# NodeNadelAdapter.net
KiCad netlist of a schematic drawn in EAGLE
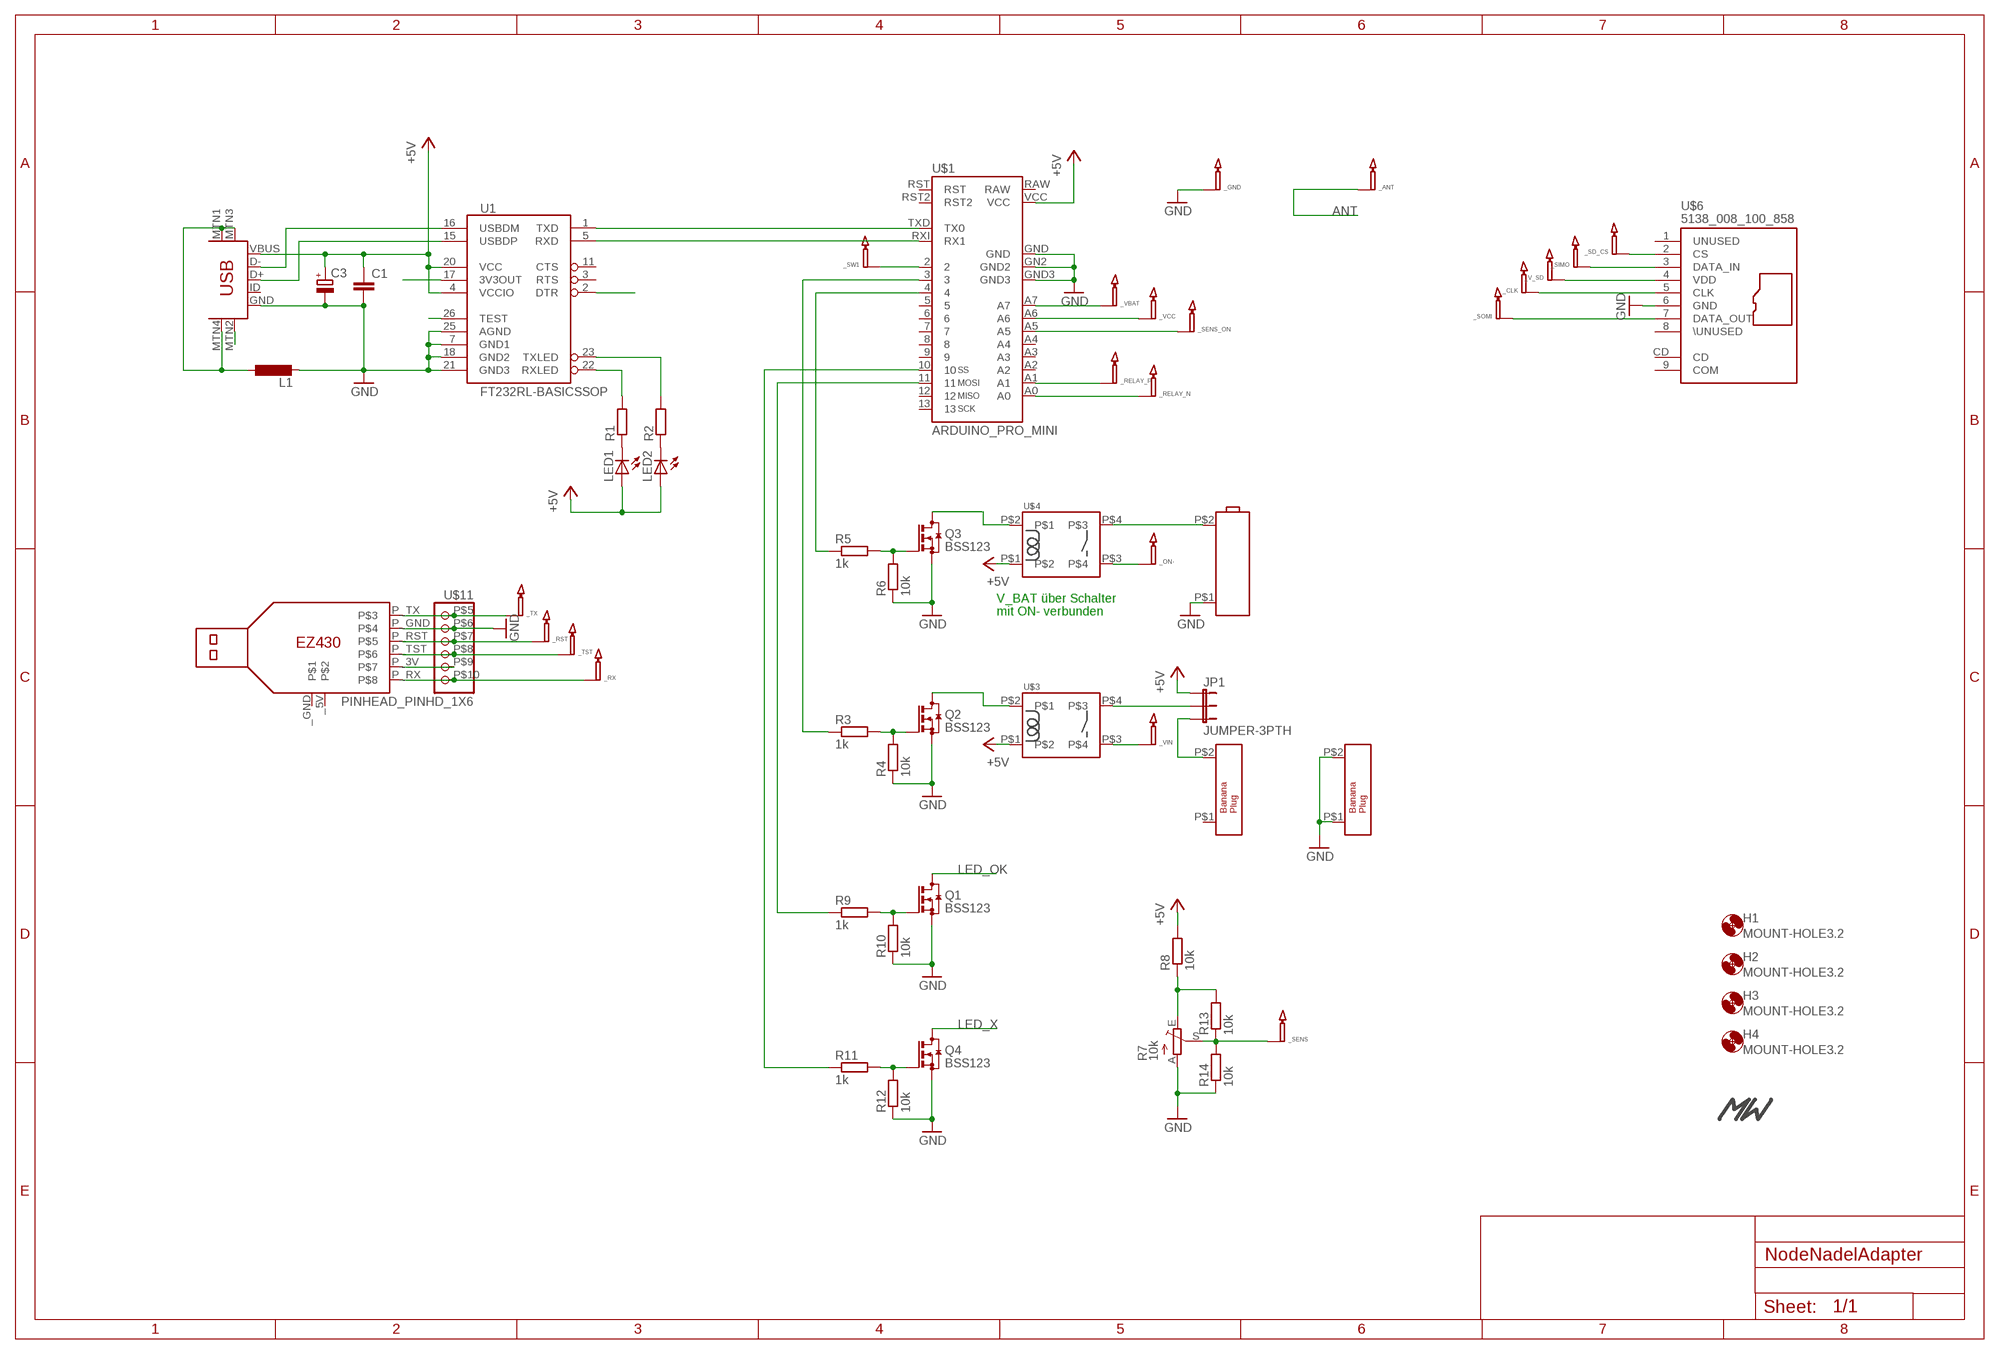
[diagram p0: schematic, sheet 1]

(export (version "E")
  (design (tool "Eeschema 10.0.6"))
  (components
    (comp (ref "C1")
      (value "C-EUC0603")
      (footprint "eagle-import:C0603")
      (libsource (lib "eagle-import") (part "C-EUC0603"))
    )
    (comp (ref "C3")
      (value "CPOL-EUSMCA")
      (footprint "eagle-import:SMC_A")
      (libsource (lib "eagle-import") (part "CPOL-EUSMCA"))
    )
    (comp (ref "H1")
      (value "MOUNT-HOLE3.2")
      (footprint "eagle-import:3,2")
      (libsource (lib "eagle-import") (part "MOUNT-HOLE3.2"))
    )
    (comp (ref "H2")
      (value "MOUNT-HOLE3.2")
      (footprint "eagle-import:3,2")
      (libsource (lib "eagle-import") (part "MOUNT-HOLE3.2"))
    )
    (comp (ref "H3")
      (value "MOUNT-HOLE3.2")
      (footprint "eagle-import:3,2")
      (libsource (lib "eagle-import") (part "MOUNT-HOLE3.2"))
    )
    (comp (ref "H4")
      (value "MOUNT-HOLE3.2")
      (footprint "eagle-import:3,2")
      (libsource (lib "eagle-import") (part "MOUNT-HOLE3.2"))
    )
    (comp (ref "JP1")
      (value "JUMPER-3PTH")
      (footprint "eagle-import:1X03")
      (libsource (lib "eagle-import") (part "JUMPER-3PTH"))
    )
    (comp (ref "L1")
      (value "L-EUL2012C")
      (footprint "eagle-import:L2012C")
      (libsource (lib "eagle-import") (part "L-EUL2012C"))
    )
    (comp (ref "LED1")
      (value "LEDSML0805")
      (footprint "eagle-import:SML0805")
      (libsource (lib "eagle-import") (part "LEDSML0805"))
    )
    (comp (ref "LED2")
      (value "LEDSML0805")
      (footprint "eagle-import:SML0805")
      (libsource (lib "eagle-import") (part "LEDSML0805"))
    )
    (comp (ref "Q1")
      (value "BSS123")
      (footprint "eagle-import:SOT23")
      (libsource (lib "eagle-import") (part "BSS123"))
    )
    (comp (ref "Q2")
      (value "BSS123")
      (footprint "eagle-import:SOT23")
      (libsource (lib "eagle-import") (part "BSS123"))
    )
    (comp (ref "Q3")
      (value "BSS123")
      (footprint "eagle-import:SOT23")
      (libsource (lib "eagle-import") (part "BSS123"))
    )
    (comp (ref "Q4")
      (value "BSS123")
      (footprint "eagle-import:SOT23")
      (libsource (lib "eagle-import") (part "BSS123"))
    )
    (comp (ref "R1")
      (value "R-EU_R0603")
      (footprint "eagle-import:R0603")
      (libsource (lib "eagle-import") (part "R-EU_R0603"))
    )
    (comp (ref "R2")
      (value "R-EU_R0603")
      (footprint "eagle-import:R0603")
      (libsource (lib "eagle-import") (part "R-EU_R0603"))
    )
    (comp (ref "R3")
      (value "1k")
      (footprint "eagle-import:R0603")
      (libsource (lib "eagle-import") (part "R-EU_R0603"))
    )
    (comp (ref "R4")
      (value "10k")
      (footprint "eagle-import:R0603")
      (libsource (lib "eagle-import") (part "R-EU_R0603"))
    )
    (comp (ref "R5")
      (value "1k")
      (footprint "eagle-import:R0603")
      (libsource (lib "eagle-import") (part "R-EU_R0603"))
    )
    (comp (ref "R6")
      (value "10k")
      (footprint "eagle-import:R0603")
      (libsource (lib "eagle-import") (part "R-EU_R0603"))
    )
    (comp (ref "R7")
      (value "10k")
      (footprint "eagle-import:CA6V")
      (libsource (lib "eagle-import") (part "TRIM_EU-CA6V"))
    )
    (comp (ref "R8")
      (value "10k")
      (footprint "eagle-import:R0603")
      (libsource (lib "eagle-import") (part "R-EU_R0603"))
    )
    (comp (ref "R9")
      (value "1k")
      (footprint "eagle-import:R0603")
      (libsource (lib "eagle-import") (part "R-EU_R0603"))
    )
    (comp (ref "R10")
      (value "10k")
      (footprint "eagle-import:R0603")
      (libsource (lib "eagle-import") (part "R-EU_R0603"))
    )
    (comp (ref "R11")
      (value "1k")
      (footprint "eagle-import:R0603")
      (libsource (lib "eagle-import") (part "R-EU_R0603"))
    )
    (comp (ref "R12")
      (value "10k")
      (footprint "eagle-import:R0603")
      (libsource (lib "eagle-import") (part "R-EU_R0603"))
    )
    (comp (ref "R13")
      (value "10k")
      (footprint "eagle-import:R0603")
      (libsource (lib "eagle-import") (part "R-EU_R0603"))
    )
    (comp (ref "R14")
      (value "10k")
      (footprint "eagle-import:R0603")
      (libsource (lib "eagle-import") (part "R-EU_R0603"))
    )
    (comp (ref "U$1")
      (value "ARDUINO_PRO_MINI")
      (footprint "eagle-import:ARDUINO_PRO_MINI")
      (libsource (lib "eagle-import") (part "ARDUINO_PRO_MINI"))
    )
    (comp (ref "U$2")
      (value "BANANA_PLUG")
      (footprint "eagle-import:BANANA_PLUG")
      (libsource (lib "eagle-import") (part "BANANA_PLUG"))
    )
    (comp (ref "U$3")
      (value "RELAY_ZETTLER_AZ767")
      (footprint "eagle-import:RELAY_ZETTLER_AZ767")
      (libsource (lib "eagle-import") (part "RELAY_ZETTLER_AZ767"))
    )
    (comp (ref "U$4")
      (value "RELAY_ZETTLER_AZ767")
      (footprint "eagle-import:RELAY_ZETTLER_AZ767")
      (libsource (lib "eagle-import") (part "RELAY_ZETTLER_AZ767"))
    )
    (comp (ref "U$5")
      (value "EZ430")
      (footprint "eagle-import:EZ430")
      (libsource (lib "eagle-import") (part "EZ430"))
    )
    (comp (ref "U$6")
      (value "5138_008_100_858")
      (footprint "eagle-import:5138_008_100_858")
      (libsource (lib "eagle-import") (part "5138_008_100_858"))
    )
    (comp (ref "U$7")
      (value "USB-MINIB-5PIN")
      (footprint "eagle-import:USB-MINIB")
      (libsource (lib "eagle-import") (part "USB-MINIB-5PIN"))
    )
    (comp (ref "U$8")
      (value "AA_BATERIE_HALTER")
      (footprint "eagle-import:AA_BATERIE_HALTER")
      (libsource (lib "eagle-import") (part "AA_BATERIE_HALTER"))
    )
    (comp (ref "U$9")
      (value "BANANA_PLUG")
      (footprint "eagle-import:BANANA_PLUG")
      (libsource (lib "eagle-import") (part "BANANA_PLUG"))
    )
    (comp (ref "U$10")
      (value "MW_LOGO")
      (footprint "eagle-import:MW_11X5MM")
      (libsource (lib "eagle-import") (part "MW_LOGO"))
    )
    (comp (ref "U$11")
      (value "PINHEAD_PINHD_1X6")
      (footprint "eagle-import:PINHEAD_1X6S")
      (libsource (lib "eagle-import") (part "PINHEAD_PINHD_1X6"))
    )
    (comp (ref "U1")
      (value "FT232RL-BASICSSOP")
      (footprint "eagle-import:SSOP28DB")
      (libsource (lib "eagle-import") (part "FT232RL-BASICSSOP"))
    )
    (comp (ref "_ANT")
      (value "POGO_PINH")
      (footprint "eagle-import:POGO_PIN_V1.5")
      (libsource (lib "eagle-import") (part "POGO_PINH"))
    )
    (comp (ref "_CLK")
      (value "POGO_PINV")
      (footprint "eagle-import:POGO_PIN_V0.9")
      (libsource (lib "eagle-import") (part "POGO_PINV"))
    )
    (comp (ref "_GND")
      (value "POGO_PINV")
      (footprint "eagle-import:POGO_PIN_V0.9")
      (libsource (lib "eagle-import") (part "POGO_PINV"))
    )
    (comp (ref "_ON-")
      (value "POGO_PINH")
      (footprint "eagle-import:POGO_PIN_V1.5")
      (libsource (lib "eagle-import") (part "POGO_PINH"))
    )
    (comp (ref "_RELAY_N")
      (value "POGO_PINH")
      (footprint "eagle-import:POGO_PIN_V1.5")
      (libsource (lib "eagle-import") (part "POGO_PINH"))
    )
    (comp (ref "_RELAY_P")
      (value "POGO_PINH")
      (footprint "eagle-import:POGO_PIN_V1.5")
      (libsource (lib "eagle-import") (part "POGO_PINH"))
    )
    (comp (ref "_RST")
      (value "POGO_PINV")
      (footprint "eagle-import:POGO_PIN_V0.9")
      (libsource (lib "eagle-import") (part "POGO_PINV"))
    )
    (comp (ref "_RX")
      (value "POGO_PINV")
      (footprint "eagle-import:POGO_PIN_V0.9")
      (libsource (lib "eagle-import") (part "POGO_PINV"))
    )
    (comp (ref "_SD_CS")
      (value "POGO_PINV")
      (footprint "eagle-import:POGO_PIN_V0.9")
      (libsource (lib "eagle-import") (part "POGO_PINV"))
    )
    (comp (ref "_SENS")
      (value "POGO_PINH")
      (footprint "eagle-import:POGO_PIN_V1.5")
      (libsource (lib "eagle-import") (part "POGO_PINH"))
    )
    (comp (ref "_SENS_ON")
      (value "POGO_PINH")
      (footprint "eagle-import:POGO_PIN_V1.5")
      (libsource (lib "eagle-import") (part "POGO_PINH"))
    )
    (comp (ref "_SIMO")
      (value "POGO_PINV")
      (footprint "eagle-import:POGO_PIN_V0.9")
      (libsource (lib "eagle-import") (part "POGO_PINV"))
    )
    (comp (ref "_SOMI")
      (value "POGO_PINV")
      (footprint "eagle-import:POGO_PIN_V0.9")
      (libsource (lib "eagle-import") (part "POGO_PINV"))
    )
    (comp (ref "_SW1")
      (value "POGO_PINV")
      (footprint "eagle-import:POGO_PIN_V0.9")
      (libsource (lib "eagle-import") (part "POGO_PINV"))
    )
    (comp (ref "_TST")
      (value "POGO_PINV")
      (footprint "eagle-import:POGO_PIN_V0.9")
      (libsource (lib "eagle-import") (part "POGO_PINV"))
    )
    (comp (ref "_TX")
      (value "POGO_PINV")
      (footprint "eagle-import:POGO_PIN_V0.9")
      (libsource (lib "eagle-import") (part "POGO_PINV"))
    )
    (comp (ref "_VBAT")
      (value "POGO_PINH")
      (footprint "eagle-import:POGO_PIN_V1.5")
      (libsource (lib "eagle-import") (part "POGO_PINH"))
    )
    (comp (ref "_VCC")
      (value "POGO_PINH")
      (footprint "eagle-import:POGO_PIN_V1.5")
      (libsource (lib "eagle-import") (part "POGO_PINH"))
    )
    (comp (ref "_VIN")
      (value "POGO_PINH")
      (footprint "eagle-import:POGO_PIN_V1.5")
      (libsource (lib "eagle-import") (part "POGO_PINH"))
    )
    (comp (ref "_V_SD")
      (value "POGO_PINV")
      (footprint "eagle-import:POGO_PIN_V0.9")
      (libsource (lib "eagle-import") (part "POGO_PINV"))
    )
  )
  (nets
    (net (code "1") (name "+5V") (class "Default")
      (node (ref "C1") (pin "1") (pinfunction "1_1") (pintype "passive"))
      (node (ref "C3") (pin "+") (pinfunction "+_+") (pintype "passive"))
      (node (ref "JP1") (pin "1") (pinfunction "1_1") (pintype "passive"))
      (node (ref "LED1") (pin "A") (pinfunction "A_A") (pintype "passive"))
      (node (ref "LED2") (pin "A") (pinfunction "A_A") (pintype "passive"))
      (node (ref "R8") (pin "2") (pinfunction "2_2") (pintype "passive"))
      (node (ref "U$1") (pin "VCC") (pinfunction "VCC_VCC") (pintype "bidirectional"))
      (node (ref "U$3") (pin "P$1") (pinfunction "P$2_P$1") (pintype "bidirectional"))
      (node (ref "U$4") (pin "P$1") (pinfunction "P$2_P$1") (pintype "bidirectional"))
      (node (ref "U$7") (pin "VBUS") (pinfunction "VBUS_VBUS") (pintype "bidirectional"))
      (node (ref "U1") (pin "20") (pinfunction "VCC_20") (pintype "power_in"))
      (node (ref "U1") (pin "4") (pinfunction "VCCIO_4") (pintype "power_in"))
    )
    (net (code "2") (name "/ANT") (class "Default")
      (node (ref "_ANT") (pin "P$1") (pinfunction "P$1_P$1") (pintype "bidirectional"))
    )
    (net (code "3") (name "/LED_OK") (class "Default")
      (node (ref "Q1") (pin "3") (pinfunction "D_3") (pintype "passive"))
    )
    (net (code "4") (name "/LED_X") (class "Default")
      (node (ref "Q4") (pin "3") (pinfunction "D_3") (pintype "passive"))
    )
    (net (code "5") (name "GND") (class "Default")
      (node (ref "C1") (pin "2") (pinfunction "2_2") (pintype "passive"))
      (node (ref "C3") (pin "-") (pinfunction "-_-") (pintype "passive"))
      (node (ref "L1") (pin "2") (pinfunction "2_2") (pintype "passive"))
      (node (ref "Q1") (pin "2") (pinfunction "S_2") (pintype "passive"))
      (node (ref "Q2") (pin "2") (pinfunction "S_2") (pintype "passive"))
      (node (ref "Q3") (pin "2") (pinfunction "S_2") (pintype "passive"))
      (node (ref "Q4") (pin "2") (pinfunction "S_2") (pintype "passive"))
      (node (ref "R10") (pin "1") (pinfunction "1_1") (pintype "passive"))
      (node (ref "R12") (pin "1") (pinfunction "1_1") (pintype "passive"))
      (node (ref "R14") (pin "1") (pinfunction "1_1") (pintype "passive"))
      (node (ref "R4") (pin "1") (pinfunction "1_1") (pintype "passive"))
      (node (ref "R6") (pin "1") (pinfunction "1_1") (pintype "passive"))
      (node (ref "R7") (pin "A") (pinfunction "A_A") (pintype "passive"))
      (node (ref "U$1") (pin "GN2") (pinfunction "GND2_GN2") (pintype "bidirectional"))
      (node (ref "U$1") (pin "GND") (pinfunction "GND_GND") (pintype "bidirectional"))
      (node (ref "U$1") (pin "GND3") (pinfunction "GND3_GND3") (pintype "bidirectional"))
      (node (ref "U$11") (pin "P$6") (pinfunction "6_P$6") (pintype "passive"))
      (node (ref "U$5") (pin "P_GND") (pinfunction "P$4_P_GND") (pintype "bidirectional"))
      (node (ref "U$6") (pin "6") (pinfunction "GND_6") (pintype "bidirectional"))
      (node (ref "U$7") (pin "GND") (pinfunction "GND_GND") (pintype "bidirectional"))
      (node (ref "U$8") (pin "P$1") (pinfunction "P$1_P$1") (pintype "bidirectional"))
      (node (ref "U$9") (pin "P$1") (pinfunction "P$1_P$1") (pintype "bidirectional"))
      (node (ref "U$9") (pin "P$2") (pinfunction "P$2_P$2") (pintype "bidirectional"))
      (node (ref "U1") (pin "18") (pinfunction "GND2_18") (pintype "power_in"))
      (node (ref "U1") (pin "21") (pinfunction "GND3_21") (pintype "power_in"))
      (node (ref "U1") (pin "25") (pinfunction "AGND_25") (pintype "power_in"))
      (node (ref "U1") (pin "7") (pinfunction "GND1_7") (pintype "power_in"))
      (node (ref "_GND") (pin "P$1") (pinfunction "P$1_P$1") (pintype "bidirectional"))
    )
    (net (code "6") (name "Net-(JP1-Pad3)") (class "Default")
      (node (ref "JP1") (pin "3") (pinfunction "3_3") (pintype "passive"))
      (node (ref "U$2") (pin "P$2") (pinfunction "P$2_P$2") (pintype "bidirectional"))
    )
    (net (code "7") (name "Net-(LED1-PadC)") (class "Default")
      (node (ref "LED1") (pin "C") (pinfunction "C_C") (pintype "passive"))
      (node (ref "R1") (pin "1") (pinfunction "1_1") (pintype "passive"))
    )
    (net (code "8") (name "Net-(LED2-PadC)") (class "Default")
      (node (ref "LED2") (pin "C") (pinfunction "C_C") (pintype "passive"))
      (node (ref "R2") (pin "1") (pinfunction "1_1") (pintype "passive"))
    )
    (net (code "9") (name "Net-(Q1-G)") (class "Default")
      (node (ref "Q1") (pin "1") (pinfunction "G_1") (pintype "passive"))
      (node (ref "R10") (pin "2") (pinfunction "2_2") (pintype "passive"))
      (node (ref "R9") (pin "2") (pinfunction "2_2") (pintype "passive"))
    )
    (net (code "10") (name "Net-(Q2-D)") (class "Default")
      (node (ref "Q2") (pin "3") (pinfunction "D_3") (pintype "passive"))
      (node (ref "U$3") (pin "P$2") (pinfunction "P$1_P$2") (pintype "bidirectional"))
    )
    (net (code "11") (name "Net-(Q2-G)") (class "Default")
      (node (ref "Q2") (pin "1") (pinfunction "G_1") (pintype "passive"))
      (node (ref "R3") (pin "2") (pinfunction "2_2") (pintype "passive"))
      (node (ref "R4") (pin "2") (pinfunction "2_2") (pintype "passive"))
    )
    (net (code "12") (name "Net-(Q3-D)") (class "Default")
      (node (ref "Q3") (pin "3") (pinfunction "D_3") (pintype "passive"))
      (node (ref "U$4") (pin "P$2") (pinfunction "P$1_P$2") (pintype "bidirectional"))
    )
    (net (code "13") (name "Net-(Q3-G)") (class "Default")
      (node (ref "Q3") (pin "1") (pinfunction "G_1") (pintype "passive"))
      (node (ref "R5") (pin "2") (pinfunction "2_2") (pintype "passive"))
      (node (ref "R6") (pin "2") (pinfunction "2_2") (pintype "passive"))
    )
    (net (code "14") (name "Net-(Q4-G)") (class "Default")
      (node (ref "Q4") (pin "1") (pinfunction "G_1") (pintype "passive"))
      (node (ref "R11") (pin "2") (pinfunction "2_2") (pintype "passive"))
      (node (ref "R12") (pin "2") (pinfunction "2_2") (pintype "passive"))
    )
    (net (code "15") (name "Net-(R3-Pad1)") (class "Default")
      (node (ref "R3") (pin "1") (pinfunction "1_1") (pintype "passive"))
      (node (ref "U$1") (pin "3") (pinfunction "3_3") (pintype "bidirectional"))
    )
    (net (code "16") (name "Net-(R5-Pad1)") (class "Default")
      (node (ref "R5") (pin "1") (pinfunction "1_1") (pintype "passive"))
      (node (ref "U$1") (pin "4") (pinfunction "4_4") (pintype "bidirectional"))
    )
    (net (code "17") (name "Net-(R9-Pad1)") (class "Default")
      (node (ref "R9") (pin "1") (pinfunction "1_1") (pintype "passive"))
      (node (ref "U$1") (pin "11") (pinfunction "11_11") (pintype "bidirectional"))
    )
    (net (code "18") (name "Net-(R11-Pad1)") (class "Default")
      (node (ref "R11") (pin "1") (pinfunction "1_1") (pintype "passive"))
      (node (ref "U$1") (pin "10") (pinfunction "10_10") (pintype "bidirectional"))
    )
    (net (code "19") (name "Net-(R13-Pad1)") (class "Default")
      (node (ref "R13") (pin "1") (pinfunction "1_1") (pintype "passive"))
      (node (ref "R14") (pin "2") (pinfunction "2_2") (pintype "passive"))
      (node (ref "R7") (pin "S") (pinfunction "S_S") (pintype "passive"))
      (node (ref "_SENS") (pin "P$1") (pinfunction "P$1_P$1") (pintype "bidirectional"))
    )
    (net (code "20") (name "Net-(R13-Pad2)") (class "Default")
      (node (ref "R13") (pin "2") (pinfunction "2_2") (pintype "passive"))
      (node (ref "R7") (pin "E") (pinfunction "E_E") (pintype "passive"))
      (node (ref "R8") (pin "1") (pinfunction "1_1") (pintype "passive"))
    )
    (net (code "21") (name "Net-(U$1-Pad2)") (class "Default")
      (node (ref "U$1") (pin "2") (pinfunction "2_2") (pintype "bidirectional"))
      (node (ref "_SW1") (pin "P$1") (pinfunction "P$1_P$1") (pintype "bidirectional"))
    )
    (net (code "22") (name "Net-(U$1-PadA0)") (class "Default")
      (node (ref "U$1") (pin "A0") (pinfunction "A0_A0") (pintype "bidirectional"))
      (node (ref "_RELAY_N") (pin "P$1") (pinfunction "P$1_P$1") (pintype "bidirectional"))
    )
    (net (code "23") (name "Net-(U$1-PadA1)") (class "Default")
      (node (ref "U$1") (pin "A1") (pinfunction "A1_A1") (pintype "bidirectional"))
      (node (ref "_RELAY_P") (pin "P$1") (pinfunction "P$1_P$1") (pintype "bidirectional"))
    )
    (net (code "24") (name "Net-(U$1-PadA5)") (class "Default")
      (node (ref "U$1") (pin "A5") (pinfunction "A5_A5") (pintype "bidirectional"))
      (node (ref "_SENS_ON") (pin "P$1") (pinfunction "P$1_P$1") (pintype "bidirectional"))
    )
    (net (code "25") (name "Net-(U$1-PadA6)") (class "Default")
      (node (ref "U$1") (pin "A6") (pinfunction "A6_A6") (pintype "bidirectional"))
      (node (ref "_VCC") (pin "P$1") (pinfunction "P$1_P$1") (pintype "bidirectional"))
    )
    (net (code "26") (name "Net-(U$1-PadA7)") (class "Default")
      (node (ref "U$1") (pin "A7") (pinfunction "A7_A7") (pintype "bidirectional"))
      (node (ref "_VBAT") (pin "P$1") (pinfunction "P$1_P$1") (pintype "bidirectional"))
    )
    (net (code "27") (name "Net-(U$1-RX1)") (class "Default")
      (node (ref "U$1") (pin "RXI") (pinfunction "RX1_RXI") (pintype "bidirectional"))
      (node (ref "U1") (pin "5") (pinfunction "RXD_5") (pintype "input"))
    )
    (net (code "28") (name "Net-(U$1-TX0)") (class "Default")
      (node (ref "U$1") (pin "TXD") (pinfunction "TX0_TXD") (pintype "bidirectional"))
      (node (ref "U1") (pin "1") (pinfunction "TXD_1") (pintype "output"))
    )
    (net (code "29") (name "Net-(U$3-P$3)") (class "Default")
      (node (ref "JP1") (pin "2") (pinfunction "2_2") (pintype "passive"))
      (node (ref "U$3") (pin "P$4") (pinfunction "P$3_P$4") (pintype "bidirectional"))
    )
    (net (code "30") (name "Net-(U$3-P$4)") (class "Default")
      (node (ref "U$3") (pin "P$3") (pinfunction "P$4_P$3") (pintype "bidirectional"))
      (node (ref "_VIN") (pin "P$1") (pinfunction "P$1_P$1") (pintype "bidirectional"))
    )
    (net (code "31") (name "Net-(U$4-P$3)") (class "Default")
      (node (ref "U$4") (pin "P$4") (pinfunction "P$3_P$4") (pintype "bidirectional"))
      (node (ref "U$8") (pin "P$2") (pinfunction "P$2_P$2") (pintype "bidirectional"))
    )
    (net (code "32") (name "Net-(U$4-P$4)") (class "Default")
      (node (ref "U$4") (pin "P$3") (pinfunction "P$4_P$3") (pintype "bidirectional"))
      (node (ref "_ON-") (pin "P$1") (pinfunction "P$1_P$1") (pintype "bidirectional"))
    )
    (net (code "33") (name "Net-(U$6-CLK)") (class "Default")
      (node (ref "U$6") (pin "5") (pinfunction "CLK_5") (pintype "bidirectional"))
      (node (ref "_CLK") (pin "P$1") (pinfunction "P$1_P$1") (pintype "bidirectional"))
    )
    (net (code "34") (name "Net-(U$6-CS)") (class "Default")
      (node (ref "U$6") (pin "2") (pinfunction "CS_2") (pintype "bidirectional"))
      (node (ref "_SD_CS") (pin "P$1") (pinfunction "P$1_P$1") (pintype "bidirectional"))
    )
    (net (code "35") (name "Net-(U$6-DATA_IN)") (class "Default")
      (node (ref "U$6") (pin "3") (pinfunction "DATA_IN_3") (pintype "bidirectional"))
      (node (ref "_SIMO") (pin "P$1") (pinfunction "P$1_P$1") (pintype "bidirectional"))
    )
    (net (code "36") (name "Net-(U$6-DATA_OUT)") (class "Default")
      (node (ref "U$6") (pin "7") (pinfunction "DATA_OUT_7") (pintype "bidirectional"))
      (node (ref "_SOMI") (pin "P$1") (pinfunction "P$1_P$1") (pintype "bidirectional"))
    )
    (net (code "37") (name "Net-(U$6-VDD)") (class "Default")
      (node (ref "U$6") (pin "4") (pinfunction "VDD_4") (pintype "bidirectional"))
      (node (ref "_V_SD") (pin "P$1") (pinfunction "P$1_P$1") (pintype "bidirectional"))
    )
    (net (code "38") (name "Net-(U$7-MTN1)") (class "Default")
      (node (ref "L1") (pin "1") (pinfunction "1_1") (pintype "passive"))
      (node (ref "U$7") (pin "MTN1") (pinfunction "MTN2_MTN1") (pintype "bidirectional"))
      (node (ref "U$7") (pin "MTN3") (pinfunction "MTN1_MTN3") (pintype "bidirectional"))
      (node (ref "U$7") (pin "MTN4") (pinfunction "MTN4_MTN4") (pintype "bidirectional"))
    )
    (net (code "39") (name "Net-(U$11-5)") (class "Default")
      (node (ref "U$11") (pin "P$5") (pinfunction "5_P$5") (pintype "passive"))
      (node (ref "U$5") (pin "P_TX") (pinfunction "P$3_P_TX") (pintype "bidirectional"))
      (node (ref "_TX") (pin "P$1") (pinfunction "P$1_P$1") (pintype "bidirectional"))
    )
    (net (code "40") (name "Net-(U$11-7)") (class "Default")
      (node (ref "U$11") (pin "P$7") (pinfunction "7_P$7") (pintype "passive"))
      (node (ref "U$5") (pin "P_RST") (pinfunction "P$5_P_RST") (pintype "bidirectional"))
      (node (ref "_RST") (pin "P$1") (pinfunction "P$1_P$1") (pintype "bidirectional"))
    )
    (net (code "41") (name "Net-(U$11-8)") (class "Default")
      (node (ref "U$11") (pin "P$8") (pinfunction "8_P$8") (pintype "passive"))
      (node (ref "U$5") (pin "P_TST") (pinfunction "P$6_P_TST") (pintype "bidirectional"))
      (node (ref "_TST") (pin "P$1") (pinfunction "P$1_P$1") (pintype "bidirectional"))
    )
    (net (code "42") (name "Net-(U$11-9)") (class "Default")
      (node (ref "U$11") (pin "P$9") (pinfunction "9_P$9") (pintype "passive"))
      (node (ref "U$5") (pin "P_3V") (pinfunction "P$7_P_3V") (pintype "bidirectional"))
    )
    (net (code "43") (name "Net-(U$11-10)") (class "Default")
      (node (ref "U$11") (pin "P$10") (pinfunction "10_P$10") (pintype "passive"))
      (node (ref "U$5") (pin "P_RX") (pinfunction "P$8_P_RX") (pintype "bidirectional"))
      (node (ref "_RX") (pin "P$1") (pinfunction "P$1_P$1") (pintype "bidirectional"))
    )
    (net (code "44") (name "Net-(U1-RXLED)") (class "Default")
      (node (ref "R1") (pin "2") (pinfunction "2_2") (pintype "passive"))
      (node (ref "U1") (pin "22") (pinfunction "RXLED_22") (pintype "bidirectional"))
    )
    (net (code "45") (name "Net-(U1-TXLED)") (class "Default")
      (node (ref "R2") (pin "2") (pinfunction "2_2") (pintype "passive"))
      (node (ref "U1") (pin "23") (pinfunction "TXLED_23") (pintype "bidirectional"))
    )
    (net (code "46") (name "Net-(U1-USBDM)") (class "Default")
      (node (ref "U$7") (pin "D-") (pinfunction "D-_D-") (pintype "bidirectional"))
      (node (ref "U1") (pin "16") (pinfunction "USBDM_16") (pintype "bidirectional"))
    )
    (net (code "47") (name "Net-(U1-USBDP)") (class "Default")
      (node (ref "U$7") (pin "D+") (pinfunction "D+_D+") (pintype "bidirectional"))
      (node (ref "U1") (pin "15") (pinfunction "USBDP_15") (pintype "bidirectional"))
    )
    (net (code "48") (name "unconnected-(U$1-Pad5)") (class "Default")
      (node (ref "U$1") (pin "5") (pinfunction "5_5") (pintype "bidirectional"))
    )
    (net (code "49") (name "unconnected-(U$1-Pad6)") (class "Default")
      (node (ref "U$1") (pin "6") (pinfunction "6_6") (pintype "bidirectional"))
    )
    (net (code "50") (name "unconnected-(U$1-Pad7)") (class "Default")
      (node (ref "U$1") (pin "7") (pinfunction "7_7") (pintype "bidirectional"))
    )
    (net (code "51") (name "unconnected-(U$1-Pad8)") (class "Default")
      (node (ref "U$1") (pin "8") (pinfunction "8_8") (pintype "bidirectional"))
    )
    (net (code "52") (name "unconnected-(U$1-Pad9)") (class "Default")
      (node (ref "U$1") (pin "9") (pinfunction "9_9") (pintype "bidirectional"))
    )
    (net (code "53") (name "unconnected-(U$1-Pad12)") (class "Default")
      (node (ref "U$1") (pin "12") (pinfunction "12_12") (pintype "bidirectional"))
    )
    (net (code "54") (name "unconnected-(U$1-Pad13)") (class "Default")
      (node (ref "U$1") (pin "13") (pinfunction "13_13") (pintype "bidirectional"))
    )
    (net (code "55") (name "unconnected-(U$1-PadA2)") (class "Default")
      (node (ref "U$1") (pin "A2") (pinfunction "A2_A2") (pintype "bidirectional"))
    )
    (net (code "56") (name "unconnected-(U$1-PadA3)") (class "Default")
      (node (ref "U$1") (pin "A3") (pinfunction "A3_A3") (pintype "bidirectional"))
    )
    (net (code "57") (name "unconnected-(U$1-PadA4)") (class "Default")
      (node (ref "U$1") (pin "A4") (pinfunction "A4_A4") (pintype "bidirectional"))
    )
    (net (code "58") (name "unconnected-(U$1-PadRAW)") (class "Default")
      (node (ref "U$1") (pin "RAW") (pinfunction "RAW_RAW") (pintype "bidirectional"))
    )
    (net (code "59") (name "unconnected-(U$1-PadRST)") (class "Default")
      (node (ref "U$1") (pin "RST") (pinfunction "RST_RST") (pintype "bidirectional"))
    )
    (net (code "60") (name "unconnected-(U$1-PadRST2)") (class "Default")
      (node (ref "U$1") (pin "RST2") (pinfunction "RST2_RST2") (pintype "bidirectional"))
    )
    (net (code "61") (name "unconnected-(U$2-PadP$1)") (class "Default")
      (node (ref "U$2") (pin "P$1") (pinfunction "P$1_P$1") (pintype "bidirectional"))
    )
    (net (code "62") (name "unconnected-(U$5-P$1-Pad_GND)") (class "Default")
      (node (ref "U$5") (pin "_GND") (pinfunction "P$1__GND") (pintype "bidirectional"))
    )
    (net (code "63") (name "unconnected-(U$5-P$2-Pad_5V)") (class "Default")
      (node (ref "U$5") (pin "_5V") (pinfunction "P$2__5V") (pintype "bidirectional"))
    )
    (net (code "64") (name "unconnected-(U$6-COM-Pad9)") (class "Default")
      (node (ref "U$6") (pin "9") (pinfunction "COM_9") (pintype "bidirectional"))
    )
    (net (code "65") (name "unconnected-(U$6-PadCD)") (class "Default")
      (node (ref "U$6") (pin "CD") (pinfunction "CD_CD") (pintype "bidirectional"))
    )
    (net (code "66") (name "unconnected-(U$6-UNUSED-Pad1)") (class "Default")
      (node (ref "U$6") (pin "1") (pinfunction "UNUSED_1") (pintype "bidirectional"))
    )
    (net (code "67") (name "unconnected-(U$6-\\UNUSED-Pad8)") (class "Default")
      (node (ref "U$6") (pin "8") (pinfunction "\\UNUSED_8") (pintype "bidirectional"))
    )
    (net (code "68") (name "unconnected-(U$7-MTN3-PadMTN2)") (class "Default")
      (node (ref "U$7") (pin "MTN2") (pinfunction "MTN3_MTN2") (pintype "bidirectional"))
    )
    (net (code "69") (name "unconnected-(U$7-PadID)") (class "Default")
      (node (ref "U$7") (pin "ID") (pinfunction "ID_ID") (pintype "bidirectional"))
    )
    (net (code "70") (name "unconnected-(U1-3V3OUT-Pad17)") (class "Default")
      (node (ref "U1") (pin "17") (pinfunction "3V3OUT_17") (pintype "output"))
    )
    (net (code "71") (name "unconnected-(U1-CTS-Pad11)") (class "Default")
      (node (ref "U1") (pin "11") (pinfunction "CTS_11") (pintype "bidirectional"))
    )
    (net (code "72") (name "unconnected-(U1-DTR-Pad2)") (class "Default")
      (node (ref "U1") (pin "2") (pinfunction "DTR_2") (pintype "bidirectional"))
    )
    (net (code "73") (name "unconnected-(U1-RTS-Pad3)") (class "Default")
      (node (ref "U1") (pin "3") (pinfunction "RTS_3") (pintype "bidirectional"))
    )
    (net (code "74") (name "unconnected-(U1-TEST-Pad26)") (class "Default")
      (node (ref "U1") (pin "26") (pinfunction "TEST_26") (pintype "input"))
    )
  )
)
